# CH32X315MCU-R0.net
KiCad netlist of a schematic drawn in Altium Designer
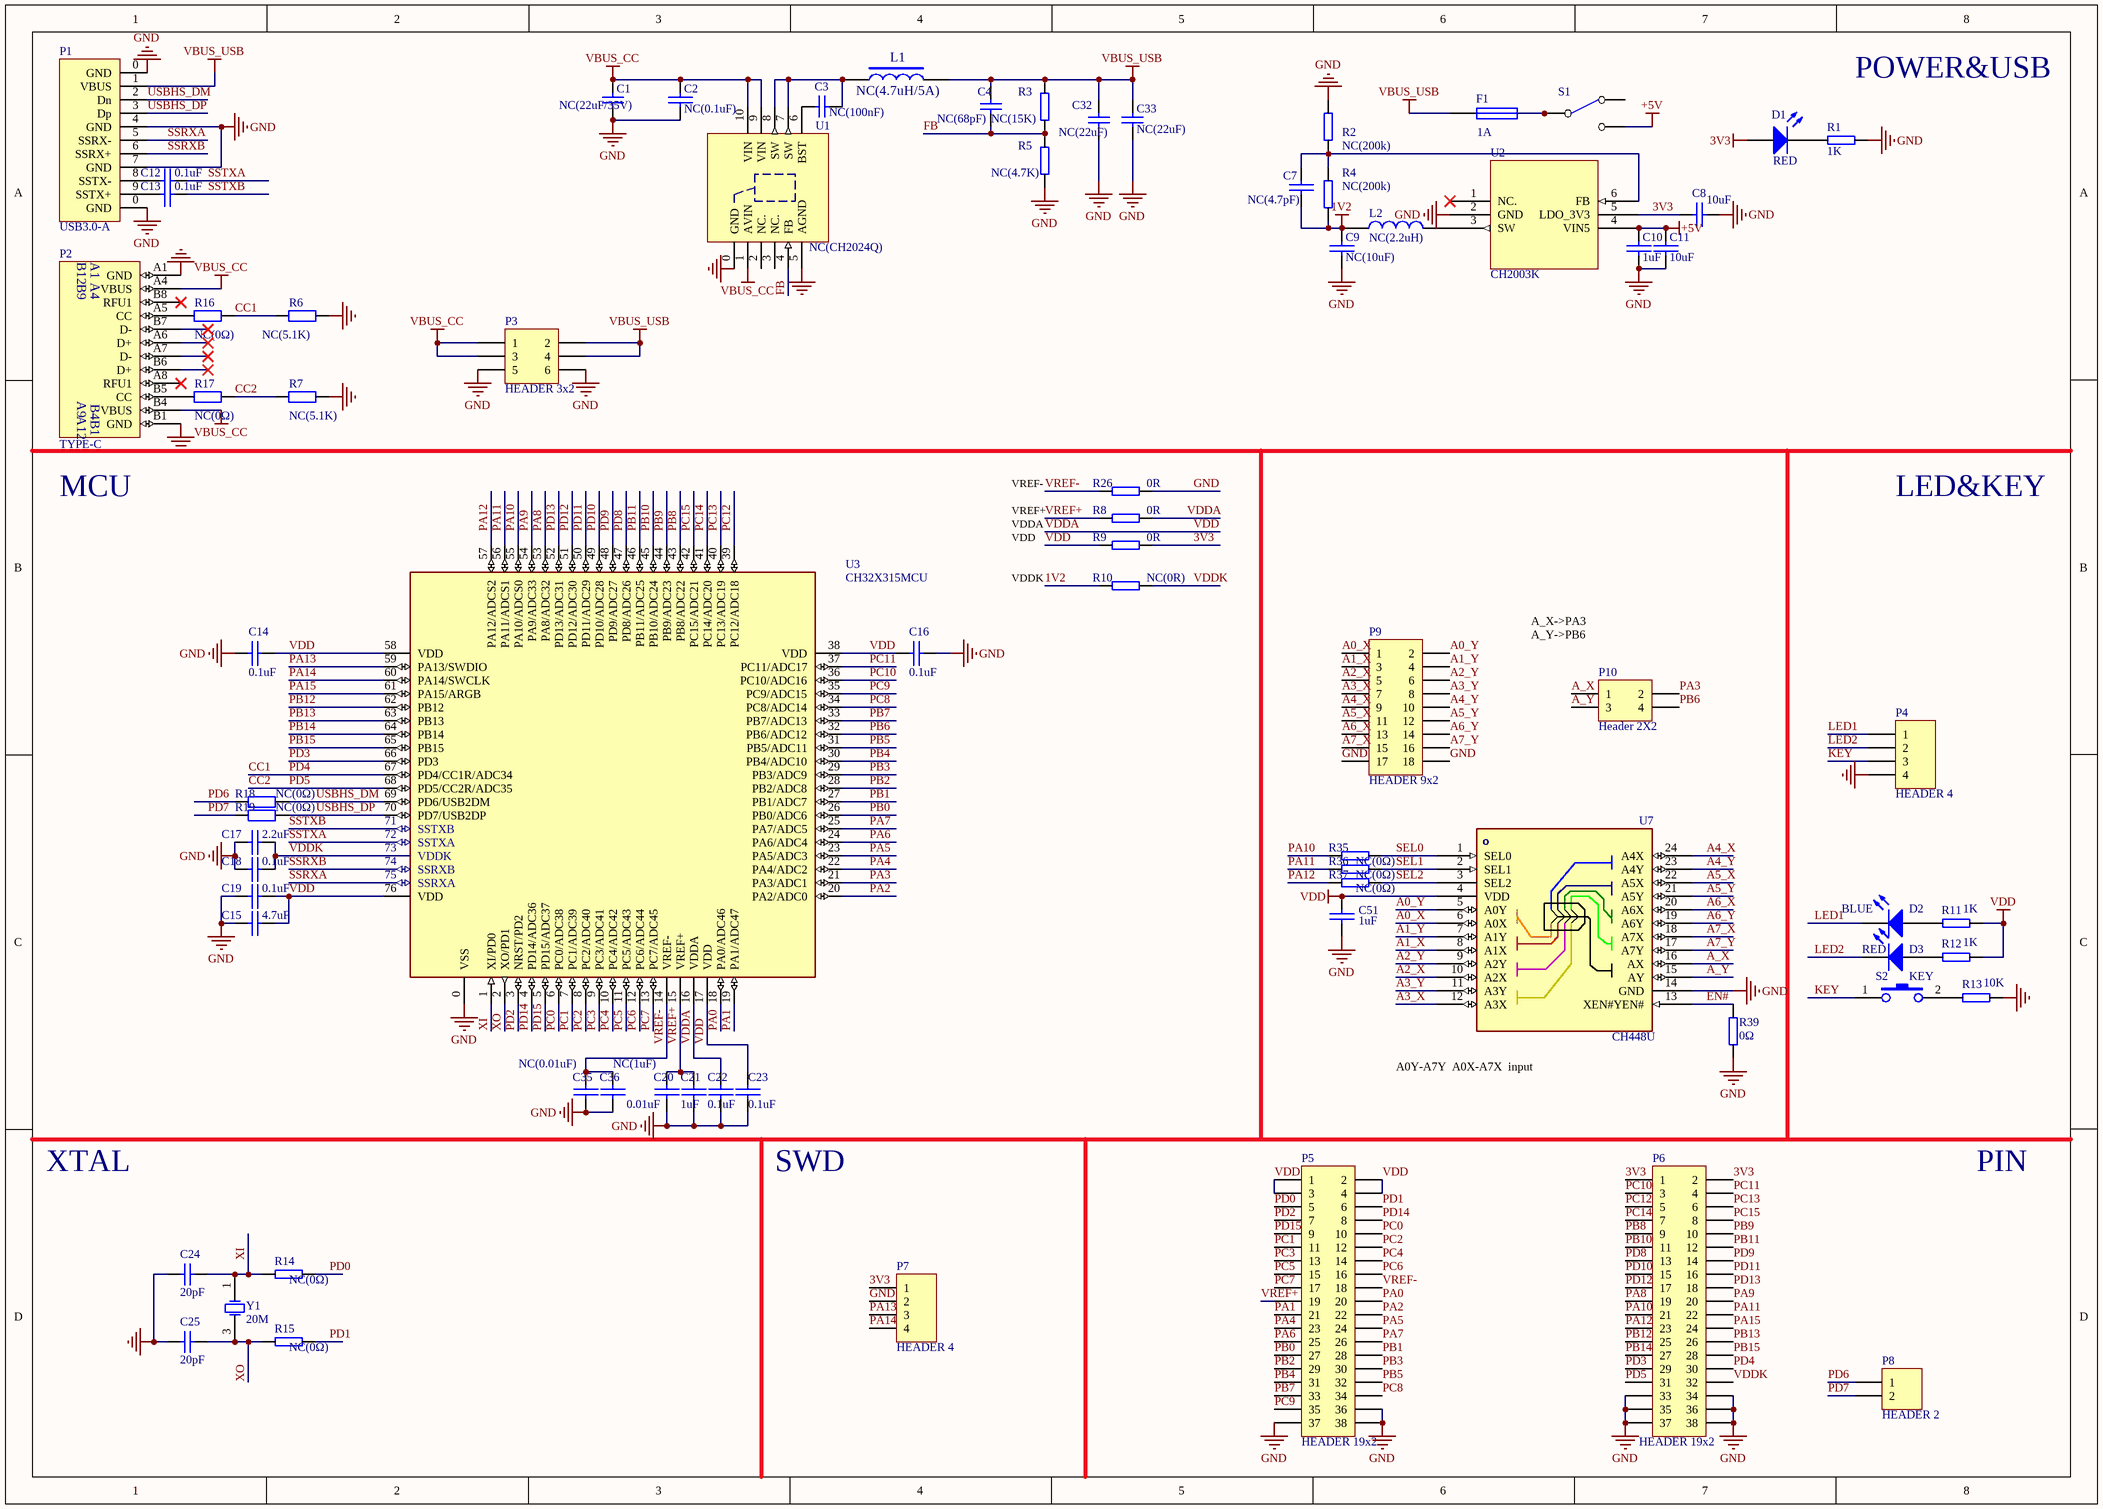
[diagram p0: CH32X315MCU-R0.SchDoc]

(export (version "E")
  (design (tool "Eeschema 10.0.6"))
  (components
    (comp (ref "C1")
      (value "NC(22uF/35V)")
      (footprint "0805_C")
      (description "贴片电容")
      (libsource (lib "Miscellaneous Devices LC") (part "0603 100nF (104) 10% 50V"))
    )
    (comp (ref "C2")
      (value "NC(0.1uF)")
      (footprint "0402_C")
      (description "Capacitor")
      (libsource (lib "") (part "CAP_1"))
    )
    (comp (ref "C3")
      (value "NC(100nF)")
      (footprint "0402_C")
      (description "贴片电容")
      (libsource (lib "Miscellaneous Devices LC") (part "0603 1uF (105) 10% 50V"))
    )
    (comp (ref "C4")
      (value "NC(68pF)")
      (footprint "0402_C")
      (description "贴片电容")
      (libsource (lib "Miscellaneous Devices LC") (part "0603 100nF (104) 10% 50V"))
    )
    (comp (ref "C7")
      (value "NC(4.7pF)")
      (footprint "0402_C")
      (description "Capacitor")
      (libsource (lib "*") (part "CAP"))
    )
    (comp (ref "C8")
      (value "10uF")
      (footprint "0603_C")
      (description "Capacitor")
      (libsource (lib "") (part "CAP_1"))
    )
    (comp (ref "C9")
      (value "NC(10uF)")
      (footprint "0603_C")
      (description "Capacitor")
      (libsource (lib "") (part "CAP_1"))
    )
    (comp (ref "C10")
      (value "1uF")
      (footprint "0402_C")
      (description "Capacitor")
      (libsource (lib "*") (part "CAP"))
    )
    (comp (ref "C11")
      (value "10uF")
      (footprint "0603_C")
      (description "Capacitor")
      (libsource (lib "") (part "CAP_1"))
    )
    (comp (ref "C12")
      (value "0.1uF")
      (footprint "0402_C")
      (description "Capacitor")
      (libsource (lib "") (part "CAP_1"))
    )
    (comp (ref "C13")
      (value "0.1uF")
      (footprint "0402_C")
      (description "Capacitor")
      (libsource (lib "") (part "CAP_1"))
    )
    (comp (ref "C14")
      (value "0.1uF")
      (footprint "0402_C")
      (description "Capacitor")
      (libsource (lib "*") (part "CAP"))
    )
    (comp (ref "C15")
      (value "4.7uF")
      (footprint "0402_C")
      (description "Capacitor")
      (libsource (lib "*") (part "CAP"))
    )
    (comp (ref "C16")
      (value "0.1uF")
      (footprint "0402_C")
      (description "Capacitor")
      (libsource (lib "*") (part "CAP"))
    )
    (comp (ref "C17")
      (value "2.2uF")
      (footprint "0402_C")
      (description "Capacitor")
      (libsource (lib "*") (part "CAP"))
    )
    (comp (ref "C18")
      (value "0.1uF")
      (footprint "0402_C")
      (description "Capacitor")
      (libsource (lib "*") (part "CAP"))
    )
    (comp (ref "C19")
      (value "0.1uF")
      (footprint "0402_C")
      (description "Capacitor")
      (libsource (lib "*") (part "CAP"))
    )
    (comp (ref "C20")
      (value "0.01uF")
      (footprint "0402_C")
      (description "Capacitor")
      (libsource (lib "*") (part "CAP"))
    )
    (comp (ref "C21")
      (value "1uF")
      (footprint "0402_C")
      (description "Capacitor")
      (libsource (lib "*") (part "CAP"))
    )
    (comp (ref "C22")
      (value "0.1uF")
      (footprint "0402_C")
      (description "Capacitor")
      (libsource (lib "*") (part "CAP"))
    )
    (comp (ref "C23")
      (value "0.1uF")
      (footprint "0402_C")
      (description "Capacitor")
      (libsource (lib "*") (part "CAP"))
    )
    (comp (ref "C24")
      (value "20pF")
      (footprint "0402_C")
      (description "Capacitor")
      (libsource (lib "Miscellaneous Devices") (part "Cap"))
    )
    (comp (ref "C25")
      (value "20pF")
      (footprint "0402_C")
      (description "Capacitor")
      (libsource (lib "Miscellaneous Devices") (part "Cap"))
    )
    (comp (ref "C32")
      (value "NC(22uF)")
      (footprint "0805_C")
      (description "贴片电容")
      (libsource (lib "Miscellaneous Devices LC") (part "0603 100nF (104) 10% 50V"))
    )
    (comp (ref "C33")
      (value "NC(22uF)")
      (footprint "0805_C")
      (description "贴片电容")
      (libsource (lib "Miscellaneous Devices LC") (part "0603 100nF (104) 10% 50V"))
    )
    (comp (ref "C35")
      (value "NC(0.01uF)")
      (footprint "0402_C")
      (description "Capacitor")
      (libsource (lib "*") (part "CAP"))
    )
    (comp (ref "C36")
      (value "NC(1uF)")
      (footprint "0402_C")
      (description "Capacitor")
      (libsource (lib "*") (part "CAP"))
    )
    (comp (ref "C51")
      (value "1uF")
      (footprint "0402_C")
      (description "Capacitor")
      (libsource (lib "wch_sch_others") (part "CAP"))
    )
    (comp (ref "D1")
      (value "RED")
      (footprint "0603+")
      (description "Typical INFRARED GaAs LED")
      (fields (field (name "PUBLISHER") "Altium Limited"))
      (libsource (lib "*") (part "LED0"))
    )
    (comp (ref "D2")
      (value "BLUE")
      (footprint "0603+")
      (description "Typical INFRARED GaAs LED")
      (fields (field (name "PUBLISHER") "Altium Limited"))
      (libsource (lib "*") (part "LED0"))
    )
    (comp (ref "D3")
      (value "RED")
      (footprint "0603+")
      (description "Typical INFRARED GaAs LED")
      (fields (field (name "PUBLISHER") "Altium Limited"))
      (libsource (lib "*") (part "LED0"))
    )
    (comp (ref "F1")
      (value "1A")
      (footprint "0603")
      (description "Fuse")
      (libsource (lib "wch_sch_others") (part "FUSE1"))
    )
    (comp (ref "L1")
      (value "NC(4.7uH/5A)")
      (footprint "IND-SMD_L7.0-W6.6")
      (libsource (lib "wch_sch_others") (part "INDUCTOR"))
    )
    (comp (ref "L2") (value "NC(2.2uH)") (footprint "CD32") (libsource (lib "*") (part "INDUCTOR")))
    (comp (ref "P1")
      (value "USB3.0-A")
      (footprint "USB3.0-A-Receptacle")
      (libsource (lib "wch_sch_others") (part "USB3.0-A"))
    )
    (comp (ref "P2")
      (value "TYPE-C")
      (footprint "TYPE-C-Receptacle-2.0")
      (libsource (lib "*") (part "TYPE-C1"))
    )
    (comp (ref "P3")
      (value "HEADER 3x2")
      (footprint "MYPCB:IDC6-2.54mm")
      (description "Header, 3-Pin, Dual row")
      (libsource (lib "wch_sch_others") (part "HEADER 3x2"))
    )
    (comp (ref "P4")
      (value "HEADER 4")
      (footprint "SIP4-2.54mm")
      (description "Header, 4-Pin")
      (libsource (lib "wch_sch_others") (part "HEADER 4"))
    )
    (comp (ref "P5")
      (value "HEADER 19x2")
      (footprint "MYPCB:IDC38-2.54MM")
      (description "Header, 19-Pin, Dual row")
      (libsource (lib "wch_sch_others") (part "HEADER 19x2"))
    )
    (comp (ref "P6")
      (value "HEADER 19x2")
      (footprint "MYPCB:IDC38-2.54MM")
      (description "Header, 19-Pin, Dual row")
      (libsource (lib "wch_sch_others") (part "HEADER 19x2"))
    )
    (comp (ref "P7")
      (value "HEADER 4")
      (footprint "SIP4-2.54mm")
      (description "Header, 4-Pin")
      (libsource (lib "wch_sch_others") (part "HEADER 4"))
    )
    (comp (ref "P8")
      (value "HEADER 2")
      (footprint "MYPCB:SIP2-2.54mm")
      (description "Header, 2-Pin")
      (libsource (lib "wch_sch_others") (part "HEADER 2"))
    )
    (comp (ref "P9")
      (value "HEADER 9x2")
      (footprint "MYPCB:IDC18-2.54MM")
      (description "Header, 9-Pin, Dual row")
      (libsource (lib "wch_sch_others") (part "HEADER 9x2"))
    )
    (comp (ref "P10")
      (value "Header 2X2")
      (footprint "IDC4-2.54mm")
      (description "Header, 2-Pin, Dual row")
      (fields (field (name "PUBLISHER") "Altium Limited"))
      (libsource (lib "Miscellaneous Connectors") (part "Header 2X2"))
    )
    (comp (ref "R1") (value "1K") (footprint "0402") (libsource (lib "") (part "RES_1")))
    (comp (ref "R2") (value "NC(200k)") (footprint "0402") (libsource (lib "wch_sch_others") (part "RES")))
    (comp (ref "R3") (value "NC(15K)") (footprint "0402") (libsource (lib "wch_sch_others(1)") (part "RES")))
    (comp (ref "R4") (value "NC(200k)") (footprint "0402") (libsource (lib "wch_sch_others") (part "RES")))
    (comp (ref "R5") (value "NC(4.7K)") (footprint "0402") (libsource (lib "wch_sch_others(1)") (part "RES")))
    (comp (ref "R6")
      (value "NC(5.1K)")
      (footprint "0402")
      (description "Resistor")
      (libsource (lib "") (part "Res2_1"))
    )
    (comp (ref "R7")
      (value "NC(5.1K)")
      (footprint "0402")
      (description "Resistor")
      (libsource (lib "") (part "Res2_1"))
    )
    (comp (ref "R8") (value "0R") (footprint "0402") (libsource (lib "*") (part "R")))
    (comp (ref "R9") (value "0R") (footprint "0402") (libsource (lib "*") (part "R")))
    (comp (ref "R10") (value "NC(0R)") (footprint "0402") (libsource (lib "*") (part "R")))
    (comp (ref "R11") (value "1K") (footprint "0402") (libsource (lib "") (part "RES_1")))
    (comp (ref "R12") (value "1K") (footprint "0402") (libsource (lib "") (part "RES_1")))
    (comp (ref "R13") (value "10K") (footprint "0402") (libsource (lib "") (part "RES_1")))
    (comp (ref "R14") (value "NC(0Ω)") (footprint "0402") (libsource (lib "wch_sch_others") (part "RES")))
    (comp (ref "R15") (value "NC(0Ω)") (footprint "0402") (libsource (lib "wch_sch_others") (part "RES")))
    (comp (ref "R16")
      (value "NC(0Ω)")
      (footprint "0402")
      (description "Resistor")
      (libsource (lib "") (part "Res2_1"))
    )
    (comp (ref "R17")
      (value "NC(0Ω)")
      (footprint "0402")
      (description "Resistor")
      (libsource (lib "") (part "Res2_1"))
    )
    (comp (ref "R18")
      (value "NC(0Ω)")
      (footprint "0402")
      (description "Resistor")
      (libsource (lib "Miscellaneous Devices") (part "Res2"))
    )
    (comp (ref "R19")
      (value "NC(0Ω)")
      (footprint "0402")
      (description "Resistor")
      (libsource (lib "Miscellaneous Devices") (part "Res2"))
    )
    (comp (ref "R26") (value "0R") (footprint "0402") (libsource (lib "*") (part "R")))
    (comp (ref "R35") (value "NC(0Ω)") (footprint "0402") (libsource (lib "wch_sch_others") (part "RES")))
    (comp (ref "R36") (value "NC(0Ω)") (footprint "0402") (libsource (lib "wch_sch_others") (part "RES")))
    (comp (ref "R37") (value "NC(0Ω)") (footprint "0402") (libsource (lib "wch_sch_others") (part "RES")))
    (comp (ref "R39") (value "0Ω") (footprint "0402") (libsource (lib "wch_sch_others") (part "RES")))
    (comp (ref "S1") (value "SW SPDT") (footprint "SW1") (libsource (lib "*") (part "SW SPDT")))
    (comp (ref "S2")
      (value "KEY")
      (footprint "SMD_6.1x3.65x2.5mm-KEY")
      (libsource (lib "wch_sch_others") (part "KEY1"))
    )
    (comp (ref "U1")
      (value "NC(CH2024Q)")
      (footprint "DFN10_3X3")
      (description "Step-Down DC-DC Converter, 28V input, FB 1.2V, 3A output")
      (libsource (lib "DHXXXSCH") (part "CH2024Q"))
    )
    (comp (ref "U2")
      (value "CH2003K")
      (footprint "SOT-23-6")
      (description "Step-Down DC-DC Converter, 5V input, FB 0.6V, 800mA output, with LDO 3.3V * 200mA")
      (libsource (lib "DHXXXSCH") (part "CH2003K"))
    )
    (comp (ref "U3")
      (value "CH32X315MCU")
      (footprint "QFN76_9X9")
      (description "RISC-V FPU MCU, 480MHz, USB3.0_5Gbps, PD, HSADC")
      (libsource (lib "DHXXXSCH") (part "CH32X315MCU"))
    )
    (comp (ref "U7")
      (value "CH448U")
      (footprint "QSOP24")
      (description "USB2.0 mux 8:1 / 16:1 Differential Switch, DPOT with dual enable")
      (libsource (lib "CH448U") (part "CH448U"))
    )
    (comp (ref "Y1")
      (value "20M")
      (footprint "XT3225")
      (description "Crystal Oscillator")
      (fields (field (name "PUBLISHER") "Altium Limited"))
      (libsource (lib "Miscellaneous Devices") (part "XTAL"))
    )
  )
  (nets
    (net (code "1") (name "+5V") (class "Default")
      (node (ref "C10") (pin "2") (pinfunction "2_2") (pintype "passive"))
      (node (ref "C11") (pin "2") (pinfunction "2_2") (pintype "passive"))
      (node (ref "S1") (pin "2") (pinfunction "NC_2") (pintype "passive"))
      (node (ref "U2") (pin "4") (pinfunction "VIN5_4") (pintype "power_in"))
    )
    (net (code "3") (name "/A0_X") (class "Default")
      (node (ref "P9") (pin "1") (pinfunction "1_1") (pintype "passive"))
      (node (ref "U7") (pin "6") (pinfunction "A0X_6") (pintype "bidirectional"))
    )
    (net (code "4") (name "/A0_Y") (class "Default")
      (node (ref "P9") (pin "2") (pinfunction "2_2") (pintype "passive"))
      (node (ref "U7") (pin "5") (pinfunction "A0Y_5") (pintype "bidirectional"))
    )
    (net (code "5") (name "/A1_X") (class "Default")
      (node (ref "P9") (pin "3") (pinfunction "3_3") (pintype "passive"))
      (node (ref "U7") (pin "8") (pinfunction "A1X_8") (pintype "bidirectional"))
    )
    (net (code "6") (name "/A1_Y") (class "Default")
      (node (ref "P9") (pin "4") (pinfunction "4_4") (pintype "passive"))
      (node (ref "U7") (pin "7") (pinfunction "A1Y_7") (pintype "bidirectional"))
    )
    (net (code "7") (name "/A2_X") (class "Default")
      (node (ref "P9") (pin "5") (pinfunction "5_5") (pintype "passive"))
      (node (ref "U7") (pin "10") (pinfunction "A2X_10") (pintype "bidirectional"))
    )
    (net (code "8") (name "/A2_Y") (class "Default")
      (node (ref "P9") (pin "6") (pinfunction "6_6") (pintype "passive"))
      (node (ref "U7") (pin "9") (pinfunction "A2Y_9") (pintype "bidirectional"))
    )
    (net (code "9") (name "/A3_X") (class "Default")
      (node (ref "P9") (pin "7") (pinfunction "7_7") (pintype "passive"))
      (node (ref "U7") (pin "12") (pinfunction "A3X_12") (pintype "bidirectional"))
    )
    (net (code "10") (name "/A3_Y") (class "Default")
      (node (ref "P9") (pin "8") (pinfunction "8_8") (pintype "passive"))
      (node (ref "U7") (pin "11") (pinfunction "A3Y_11") (pintype "bidirectional"))
    )
    (net (code "11") (name "/A4_X") (class "Default")
      (node (ref "P9") (pin "9") (pinfunction "9_9") (pintype "passive"))
      (node (ref "U7") (pin "24") (pinfunction "A4X_24") (pintype "bidirectional"))
    )
    (net (code "12") (name "/A4_Y") (class "Default")
      (node (ref "P9") (pin "10") (pinfunction "10_10") (pintype "passive"))
      (node (ref "U7") (pin "23") (pinfunction "A4Y_23") (pintype "bidirectional"))
    )
    (net (code "13") (name "/A5_X") (class "Default")
      (node (ref "P9") (pin "11") (pinfunction "11_11") (pintype "passive"))
      (node (ref "U7") (pin "22") (pinfunction "A5X_22") (pintype "bidirectional"))
    )
    (net (code "14") (name "/A5_Y") (class "Default")
      (node (ref "P9") (pin "12") (pinfunction "12_12") (pintype "passive"))
      (node (ref "U7") (pin "21") (pinfunction "A5Y_21") (pintype "bidirectional"))
    )
    (net (code "15") (name "/A6_X") (class "Default")
      (node (ref "P9") (pin "13") (pinfunction "13_13") (pintype "passive"))
      (node (ref "U7") (pin "20") (pinfunction "A6X_20") (pintype "bidirectional"))
    )
    (net (code "16") (name "/A6_Y") (class "Default")
      (node (ref "P9") (pin "14") (pinfunction "14_14") (pintype "passive"))
      (node (ref "U7") (pin "19") (pinfunction "A6Y_19") (pintype "bidirectional"))
    )
    (net (code "17") (name "/A7_X") (class "Default")
      (node (ref "P9") (pin "15") (pinfunction "15_15") (pintype "passive"))
      (node (ref "U7") (pin "18") (pinfunction "A7X_18") (pintype "bidirectional"))
    )
    (net (code "18") (name "/A7_Y") (class "Default")
      (node (ref "P9") (pin "16") (pinfunction "16_16") (pintype "passive"))
      (node (ref "U7") (pin "17") (pinfunction "A7Y_17") (pintype "bidirectional"))
    )
    (net (code "19") (name "/A_X") (class "Default")
      (node (ref "P10") (pin "1") (pinfunction "1_1") (pintype "passive"))
      (node (ref "U7") (pin "16") (pinfunction "AX_16") (pintype "bidirectional"))
    )
    (net (code "20") (name "/A_Y") (class "Default")
      (node (ref "P10") (pin "3") (pinfunction "3_3") (pintype "passive"))
      (node (ref "U7") (pin "15") (pinfunction "AY_15") (pintype "bidirectional"))
    )
    (net (code "21") (name "/CC1") (class "Default")
      (node (ref "P6") (pin "30") (pinfunction "30_30") (pintype "passive"))
      (node (ref "R16") (pin "2") (pinfunction "2_2") (pintype "passive"))
      (node (ref "R6") (pin "1") (pinfunction "1_1") (pintype "passive"))
      (node (ref "U3") (pin "67") (pinfunction "PD4/CC1R/ADC34_67") (pintype "bidirectional"))
    )
    (net (code "22") (name "/CC2") (class "Default")
      (node (ref "P6") (pin "31") (pinfunction "31_31") (pintype "passive"))
      (node (ref "R17") (pin "2") (pinfunction "2_2") (pintype "passive"))
      (node (ref "R7") (pin "1") (pinfunction "1_1") (pintype "passive"))
      (node (ref "U3") (pin "68") (pinfunction "PD5/CC2R/ADC35_68") (pintype "bidirectional"))
    )
    (net (code "23") (name "/EN#") (class "Default")
      (node (ref "R39") (pin "2") (pintype "passive"))
      (node (ref "U7") (pin "13") (pinfunction "XEN#YEN#_13") (pintype "input"))
    )
    (net (code "24") (name "/FB") (class "Default")
      (node (ref "C4") (pin "2") (pinfunction "2_2") (pintype "passive"))
      (node (ref "R3") (pin "1") (pintype "passive"))
      (node (ref "R5") (pin "2") (pintype "passive"))
      (node (ref "U1") (pin "4") (pinfunction "FB_4") (pintype "input"))
    )
    (net (code "25") (name "/KEY") (class "Default")
      (node (ref "P4") (pin "3") (pinfunction "3_3") (pintype "passive"))
      (node (ref "S2") (pin "1") (pinfunction "1_1") (pintype "passive"))
    )
    (net (code "26") (name "/LED1") (class "Default")
      (node (ref "D2") (pin "2") (pinfunction "K_2") (pintype "passive"))
      (node (ref "P4") (pin "1") (pinfunction "1_1") (pintype "passive"))
    )
    (net (code "27") (name "/LED2") (class "Default")
      (node (ref "D3") (pin "2") (pinfunction "K_2") (pintype "passive"))
      (node (ref "P4") (pin "2") (pinfunction "2_2") (pintype "passive"))
    )
    (net (code "28") (name "/PA0") (class "Default")
      (node (ref "P5") (pin "20") (pinfunction "20_20") (pintype "passive"))
      (node (ref "U3") (pin "18") (pinfunction "PA0/ADC46_18") (pintype "bidirectional"))
    )
    (net (code "29") (name "/PA1") (class "Default")
      (node (ref "P5") (pin "21") (pinfunction "21_21") (pintype "passive"))
      (node (ref "U3") (pin "19") (pinfunction "PA1/ADC47_19") (pintype "bidirectional"))
    )
    (net (code "30") (name "/PA2") (class "Default")
      (node (ref "P5") (pin "22") (pinfunction "22_22") (pintype "passive"))
      (node (ref "U3") (pin "20") (pinfunction "PA2/ADC0_20") (pintype "bidirectional"))
    )
    (net (code "31") (name "/PA3") (class "Default")
      (node (ref "P10") (pin "2") (pinfunction "2_2") (pintype "passive"))
      (node (ref "U3") (pin "21") (pinfunction "PA3/ADC1_21") (pintype "bidirectional"))
    )
    (net (code "32") (name "/PA4") (class "Default")
      (node (ref "P5") (pin "23") (pinfunction "23_23") (pintype "passive"))
      (node (ref "U3") (pin "22") (pinfunction "PA4/ADC2_22") (pintype "bidirectional"))
    )
    (net (code "33") (name "/PA5") (class "Default")
      (node (ref "P5") (pin "24") (pinfunction "24_24") (pintype "passive"))
      (node (ref "U3") (pin "23") (pinfunction "PA5/ADC3_23") (pintype "bidirectional"))
    )
    (net (code "34") (name "/PA6") (class "Default")
      (node (ref "P5") (pin "25") (pinfunction "25_25") (pintype "passive"))
      (node (ref "U3") (pin "24") (pinfunction "PA6/ADC4_24") (pintype "bidirectional"))
    )
    (net (code "35") (name "/PA7") (class "Default")
      (node (ref "P5") (pin "26") (pinfunction "26_26") (pintype "passive"))
      (node (ref "U3") (pin "25") (pinfunction "PA7/ADC5_25") (pintype "bidirectional"))
    )
    (net (code "36") (name "/PA8") (class "Default")
      (node (ref "P6") (pin "19") (pinfunction "19_19") (pintype "passive"))
      (node (ref "U3") (pin "53") (pinfunction "PA8/ADC32_53") (pintype "bidirectional"))
    )
    (net (code "37") (name "/PA9") (class "Default")
      (node (ref "P6") (pin "20") (pinfunction "20_20") (pintype "passive"))
      (node (ref "U3") (pin "54") (pinfunction "PA9/ADC33_54") (pintype "bidirectional"))
    )
    (net (code "38") (name "/PA10") (class "Default")
      (node (ref "P6") (pin "21") (pinfunction "21_21") (pintype "passive"))
      (node (ref "R35") (pin "2") (pintype "passive"))
      (node (ref "U3") (pin "55") (pinfunction "PA10/ADCS0_55") (pintype "bidirectional"))
    )
    (net (code "39") (name "/PA11") (class "Default")
      (node (ref "P6") (pin "22") (pinfunction "22_22") (pintype "passive"))
      (node (ref "R36") (pin "2") (pintype "passive"))
      (node (ref "U3") (pin "56") (pinfunction "PA11/ADCS1_56") (pintype "bidirectional"))
    )
    (net (code "40") (name "/PA12") (class "Default")
      (node (ref "P6") (pin "23") (pinfunction "23_23") (pintype "passive"))
      (node (ref "R37") (pin "2") (pintype "passive"))
      (node (ref "U3") (pin "57") (pinfunction "PA12/ADCS2_57") (pintype "bidirectional"))
    )
    (net (code "41") (name "/PA13") (class "Default")
      (node (ref "P7") (pin "3") (pinfunction "3_3") (pintype "passive"))
      (node (ref "U3") (pin "59") (pinfunction "PA13/SWDIO_59") (pintype "bidirectional"))
    )
    (net (code "42") (name "/PA14") (class "Default")
      (node (ref "P7") (pin "4") (pinfunction "4_4") (pintype "passive"))
      (node (ref "U3") (pin "60") (pinfunction "PA14/SWCLK_60") (pintype "bidirectional"))
    )
    (net (code "43") (name "/PA15") (class "Default")
      (node (ref "P6") (pin "24") (pinfunction "24_24") (pintype "passive"))
      (node (ref "U3") (pin "61") (pinfunction "PA15/ARGB_61") (pintype "bidirectional"))
    )
    (net (code "44") (name "/PB0") (class "Default")
      (node (ref "P5") (pin "27") (pinfunction "27_27") (pintype "passive"))
      (node (ref "U3") (pin "26") (pinfunction "PB0/ADC6_26") (pintype "bidirectional"))
    )
    (net (code "45") (name "/PB1") (class "Default")
      (node (ref "P5") (pin "28") (pinfunction "28_28") (pintype "passive"))
      (node (ref "U3") (pin "27") (pinfunction "PB1/ADC7_27") (pintype "bidirectional"))
    )
    (net (code "46") (name "/PB2") (class "Default")
      (node (ref "P5") (pin "29") (pinfunction "29_29") (pintype "passive"))
      (node (ref "U3") (pin "28") (pinfunction "PB2/ADC8_28") (pintype "bidirectional"))
    )
    (net (code "47") (name "/PB3") (class "Default")
      (node (ref "P5") (pin "30") (pinfunction "30_30") (pintype "passive"))
      (node (ref "U3") (pin "29") (pinfunction "PB3/ADC9_29") (pintype "bidirectional"))
    )
    (net (code "48") (name "/PB4") (class "Default")
      (node (ref "P5") (pin "31") (pinfunction "31_31") (pintype "passive"))
      (node (ref "U3") (pin "30") (pinfunction "PB4/ADC10_30") (pintype "bidirectional"))
    )
    (net (code "49") (name "/PB5") (class "Default")
      (node (ref "P5") (pin "32") (pinfunction "32_32") (pintype "passive"))
      (node (ref "U3") (pin "31") (pinfunction "PB5/ADC11_31") (pintype "bidirectional"))
    )
    (net (code "50") (name "/PB6") (class "Default")
      (node (ref "P10") (pin "4") (pinfunction "4_4") (pintype "passive"))
      (node (ref "U3") (pin "32") (pinfunction "PB6/ADC12_32") (pintype "bidirectional"))
    )
    (net (code "51") (name "/PB7") (class "Default")
      (node (ref "P5") (pin "33") (pinfunction "33_33") (pintype "passive"))
      (node (ref "U3") (pin "33") (pinfunction "PB7/ADC13_33") (pintype "bidirectional"))
    )
    (net (code "52") (name "/PB8") (class "Default")
      (node (ref "P6") (pin "9") (pinfunction "9_9") (pintype "passive"))
      (node (ref "U3") (pin "43") (pinfunction "PB8/ADC22_43") (pintype "bidirectional"))
    )
    (net (code "53") (name "/PB9") (class "Default")
      (node (ref "P6") (pin "10") (pinfunction "10_10") (pintype "passive"))
      (node (ref "U3") (pin "44") (pinfunction "PB9/ADC23_44") (pintype "bidirectional"))
    )
    (net (code "54") (name "/PB10") (class "Default")
      (node (ref "P6") (pin "11") (pinfunction "11_11") (pintype "passive"))
      (node (ref "U3") (pin "45") (pinfunction "PB10/ADC24_45") (pintype "bidirectional"))
    )
    (net (code "55") (name "/PB11") (class "Default")
      (node (ref "P6") (pin "12") (pinfunction "12_12") (pintype "passive"))
      (node (ref "U3") (pin "46") (pinfunction "PB11/ADC25_46") (pintype "bidirectional"))
    )
    (net (code "56") (name "/PB12") (class "Default")
      (node (ref "P6") (pin "25") (pinfunction "25_25") (pintype "passive"))
      (node (ref "U3") (pin "62") (pinfunction "PB12_62") (pintype "bidirectional"))
    )
    (net (code "57") (name "/PB13") (class "Default")
      (node (ref "P6") (pin "26") (pinfunction "26_26") (pintype "passive"))
      (node (ref "U3") (pin "63") (pinfunction "PB13_63") (pintype "bidirectional"))
    )
    (net (code "58") (name "/PB14") (class "Default")
      (node (ref "P6") (pin "27") (pinfunction "27_27") (pintype "passive"))
      (node (ref "U3") (pin "64") (pinfunction "PB14_64") (pintype "bidirectional"))
    )
    (net (code "59") (name "/PB15") (class "Default")
      (node (ref "P6") (pin "28") (pinfunction "28_28") (pintype "passive"))
      (node (ref "U3") (pin "65") (pinfunction "PB15_65") (pintype "bidirectional"))
    )
    (net (code "60") (name "/PC0") (class "Default")
      (node (ref "P5") (pin "10") (pinfunction "10_10") (pintype "passive"))
      (node (ref "U3") (pin "6") (pinfunction "PC0/ADC38_6") (pintype "bidirectional"))
    )
    (net (code "61") (name "/PC1") (class "Default")
      (node (ref "P5") (pin "11") (pinfunction "11_11") (pintype "passive"))
      (node (ref "U3") (pin "7") (pinfunction "PC1/ADC39_7") (pintype "bidirectional"))
    )
    (net (code "62") (name "/PC2") (class "Default")
      (node (ref "P5") (pin "12") (pinfunction "12_12") (pintype "passive"))
      (node (ref "U3") (pin "8") (pinfunction "PC2/ADC40_8") (pintype "bidirectional"))
    )
    (net (code "63") (name "/PC3") (class "Default")
      (node (ref "P5") (pin "13") (pinfunction "13_13") (pintype "passive"))
      (node (ref "U3") (pin "9") (pinfunction "PC3/ADC41_9") (pintype "bidirectional"))
    )
    (net (code "64") (name "/PC4") (class "Default")
      (node (ref "P5") (pin "14") (pinfunction "14_14") (pintype "passive"))
      (node (ref "U3") (pin "10") (pinfunction "PC4/ADC42_10") (pintype "bidirectional"))
    )
    (net (code "65") (name "/PC5") (class "Default")
      (node (ref "P5") (pin "15") (pinfunction "15_15") (pintype "passive"))
      (node (ref "U3") (pin "11") (pinfunction "PC5/ADC43_11") (pintype "bidirectional"))
    )
    (net (code "66") (name "/PC6") (class "Default")
      (node (ref "P5") (pin "16") (pinfunction "16_16") (pintype "passive"))
      (node (ref "U3") (pin "12") (pinfunction "PC6/ADC44_12") (pintype "bidirectional"))
    )
    (net (code "67") (name "/PC7") (class "Default")
      (node (ref "P5") (pin "17") (pinfunction "17_17") (pintype "passive"))
      (node (ref "U3") (pin "13") (pinfunction "PC7/ADC45_13") (pintype "bidirectional"))
    )
    (net (code "68") (name "/PC8") (class "Default")
      (node (ref "P5") (pin "34") (pinfunction "34_34") (pintype "passive"))
      (node (ref "U3") (pin "34") (pinfunction "PC8/ADC14_34") (pintype "bidirectional"))
    )
    (net (code "69") (name "/PC9") (class "Default")
      (node (ref "P5") (pin "35") (pinfunction "35_35") (pintype "passive"))
      (node (ref "U3") (pin "35") (pinfunction "PC9/ADC15_35") (pintype "bidirectional"))
    )
    (net (code "70") (name "/PC10") (class "Default")
      (node (ref "P6") (pin "3") (pinfunction "3_3") (pintype "passive"))
      (node (ref "U3") (pin "36") (pinfunction "PC10/ADC16_36") (pintype "bidirectional"))
    )
    (net (code "71") (name "/PC11") (class "Default")
      (node (ref "P6") (pin "4") (pinfunction "4_4") (pintype "passive"))
      (node (ref "U3") (pin "37") (pinfunction "PC11/ADC17_37") (pintype "bidirectional"))
    )
    (net (code "72") (name "/PC12") (class "Default")
      (node (ref "P6") (pin "5") (pinfunction "5_5") (pintype "passive"))
      (node (ref "U3") (pin "39") (pinfunction "PC12/ADC18_39") (pintype "bidirectional"))
    )
    (net (code "73") (name "/PC13") (class "Default")
      (node (ref "P6") (pin "6") (pinfunction "6_6") (pintype "passive"))
      (node (ref "U3") (pin "40") (pinfunction "PC13/ADC19_40") (pintype "bidirectional"))
    )
    (net (code "74") (name "/PC14") (class "Default")
      (node (ref "P6") (pin "7") (pinfunction "7_7") (pintype "passive"))
      (node (ref "U3") (pin "41") (pinfunction "PC14/ADC20_41") (pintype "bidirectional"))
    )
    (net (code "75") (name "/PC15") (class "Default")
      (node (ref "P6") (pin "8") (pinfunction "8_8") (pintype "passive"))
      (node (ref "U3") (pin "42") (pinfunction "PC15/ADC21_42") (pintype "bidirectional"))
    )
    (net (code "76") (name "/PD0") (class "Default")
      (node (ref "P5") (pin "5") (pinfunction "5_5") (pintype "passive"))
      (node (ref "R14") (pin "1") (pintype "passive"))
    )
    (net (code "77") (name "/PD1") (class "Default")
      (node (ref "P5") (pin "6") (pinfunction "6_6") (pintype "passive"))
      (node (ref "R15") (pin "1") (pintype "passive"))
    )
    (net (code "78") (name "/PD2") (class "Default")
      (node (ref "P5") (pin "7") (pinfunction "7_7") (pintype "passive"))
      (node (ref "U3") (pin "3") (pinfunction "NRST/PD2_3") (pintype "bidirectional"))
    )
    (net (code "79") (name "/PD3") (class "Default")
      (node (ref "P6") (pin "29") (pinfunction "29_29") (pintype "passive"))
      (node (ref "U3") (pin "66") (pinfunction "PD3_66") (pintype "bidirectional"))
    )
    (net (code "80") (name "/PD6") (class "Default")
      (node (ref "P8") (pin "1") (pinfunction "1_1") (pintype "passive"))
      (node (ref "R18") (pin "2") (pinfunction "2_2") (pintype "passive"))
    )
    (net (code "81") (name "/PD7") (class "Default")
      (node (ref "P8") (pin "2") (pinfunction "2_2") (pintype "passive"))
      (node (ref "R19") (pin "2") (pinfunction "2_2") (pintype "passive"))
    )
    (net (code "82") (name "/PD8") (class "Default")
      (node (ref "P6") (pin "13") (pinfunction "13_13") (pintype "passive"))
      (node (ref "U3") (pin "47") (pinfunction "PD8/ADC26_47") (pintype "bidirectional"))
    )
    (net (code "83") (name "/PD9") (class "Default")
      (node (ref "P6") (pin "14") (pinfunction "14_14") (pintype "passive"))
      (node (ref "U3") (pin "48") (pinfunction "PD9/ADC27_48") (pintype "bidirectional"))
    )
    (net (code "84") (name "/PD10") (class "Default")
      (node (ref "P6") (pin "15") (pinfunction "15_15") (pintype "passive"))
      (node (ref "U3") (pin "49") (pinfunction "PD10/ADC28_49") (pintype "bidirectional"))
    )
    (net (code "85") (name "/PD11") (class "Default")
      (node (ref "P6") (pin "16") (pinfunction "16_16") (pintype "passive"))
      (node (ref "U3") (pin "50") (pinfunction "PD11/ADC29_50") (pintype "bidirectional"))
    )
    (net (code "86") (name "/PD12") (class "Default")
      (node (ref "P6") (pin "17") (pinfunction "17_17") (pintype "passive"))
      (node (ref "U3") (pin "51") (pinfunction "PD12/ADC30_51") (pintype "bidirectional"))
    )
    (net (code "87") (name "/PD13") (class "Default")
      (node (ref "P6") (pin "18") (pinfunction "18_18") (pintype "passive"))
      (node (ref "U3") (pin "52") (pinfunction "PD13/ADC31_52") (pintype "bidirectional"))
    )
    (net (code "88") (name "/PD14") (class "Default")
      (node (ref "P5") (pin "8") (pinfunction "8_8") (pintype "passive"))
      (node (ref "U3") (pin "4") (pinfunction "PD14/ADC36_4") (pintype "bidirectional"))
    )
    (net (code "89") (name "/PD15") (class "Default")
      (node (ref "P5") (pin "9") (pinfunction "9_9") (pintype "passive"))
      (node (ref "U3") (pin "5") (pinfunction "PD15/ADC37_5") (pintype "bidirectional"))
    )
    (net (code "90") (name "/SEL0") (class "Default")
      (node (ref "R35") (pin "1") (pintype "passive"))
      (node (ref "U7") (pin "1") (pinfunction "SEL0_1") (pintype "input"))
    )
    (net (code "91") (name "/SEL1") (class "Default")
      (node (ref "R36") (pin "1") (pintype "passive"))
      (node (ref "U7") (pin "2") (pinfunction "SEL1_2") (pintype "input"))
    )
    (net (code "92") (name "/SEL2") (class "Default")
      (node (ref "R37") (pin "1") (pintype "passive"))
      (node (ref "U7") (pin "3") (pinfunction "SEL2_3") (pintype "power_in"))
    )
    (net (code "93") (name "/SSRXA") (class "Default")
      (node (ref "P1") (pin "5") (pinfunction "SSRX-_5") (pintype "passive"))
      (node (ref "U3") (pin "75") (pinfunction "SSRXA_75") (pintype "bidirectional"))
    )
    (net (code "94") (name "/SSRXB") (class "Default")
      (node (ref "P1") (pin "6") (pinfunction "SSRX+_6") (pintype "passive"))
      (node (ref "U3") (pin "74") (pinfunction "SSRXB_74") (pintype "bidirectional"))
    )
    (net (code "95") (name "/SSTXA") (class "Default")
      (node (ref "C12") (pin "2") (pinfunction "2_2") (pintype "passive"))
      (node (ref "U3") (pin "72") (pinfunction "SSTXA_72") (pintype "bidirectional"))
    )
    (net (code "96") (name "/SSTXB") (class "Default")
      (node (ref "C13") (pin "2") (pinfunction "2_2") (pintype "passive"))
      (node (ref "U3") (pin "71") (pinfunction "SSTXB_71") (pintype "bidirectional"))
    )
    (net (code "97") (name "/USBHS_DM") (class "Default")
      (node (ref "P1") (pin "2") (pinfunction "Dn_2") (pintype "passive"))
      (node (ref "R18") (pin "1") (pinfunction "1_1") (pintype "passive"))
      (node (ref "U3") (pin "69") (pinfunction "PD6/USB2DM_69") (pintype "bidirectional"))
    )
    (net (code "98") (name "/USBHS_DP") (class "Default")
      (node (ref "P1") (pin "3") (pinfunction "Dp_3") (pintype "passive"))
      (node (ref "R19") (pin "1") (pinfunction "1_1") (pintype "passive"))
      (node (ref "U3") (pin "70") (pinfunction "PD7/USB2DP_70") (pintype "bidirectional"))
    )
    (net (code "99") (name "/VDDK") (class "Default")
      (node (ref "C17") (pin "1") (pinfunction "1_1") (pintype "passive"))
      (node (ref "C18") (pin "1") (pinfunction "1_1") (pintype "passive"))
      (node (ref "P6") (pin "32") (pinfunction "32_32") (pintype "passive"))
      (node (ref "R10") (pin "1") (pinfunction "1_1") (pintype "passive"))
      (node (ref "U3") (pin "73") (pinfunction "VDDK_73") (pintype "power_in"))
    )
    (net (code "100") (name "/VREF+") (class "Default")
      (node (ref "C20") (pin "1") (pinfunction "1_1") (pintype "passive"))
      (node (ref "C21") (pin "1") (pinfunction "1_1") (pintype "passive"))
      (node (ref "P5") (pin "19") (pinfunction "19_19") (pintype "passive"))
      (node (ref "R8") (pin "2") (pinfunction "2_2") (pintype "passive"))
      (node (ref "U3") (pin "15") (pinfunction "VREF+_15") (pintype "power_in"))
    )
    (net (code "101") (name "/VREF-") (class "Default")
      (node (ref "C35") (pin "1") (pinfunction "1_1") (pintype "passive"))
      (node (ref "C36") (pin "1") (pinfunction "1_1") (pintype "passive"))
      (node (ref "P5") (pin "18") (pinfunction "18_18") (pintype "passive"))
      (node (ref "R26") (pin "2") (pinfunction "2_2") (pintype "passive"))
      (node (ref "U3") (pin "14") (pinfunction "VREF-_14") (pintype "power_in"))
    )
    (net (code "102") (name "/XI") (class "Default")
      (node (ref "C24") (pin "1") (pinfunction "1_1") (pintype "passive"))
      (node (ref "R14") (pin "2") (pintype "passive"))
      (node (ref "U3") (pin "1") (pinfunction "XI/PD0_1") (pintype "input"))
      (node (ref "Y1") (pin "1") (pinfunction "OSC1_1") (pintype "passive"))
    )
    (net (code "103") (name "/XO") (class "Default")
      (node (ref "C25") (pin "1") (pinfunction "1_1") (pintype "passive"))
      (node (ref "R15") (pin "2") (pintype "passive"))
      (node (ref "U3") (pin "2") (pinfunction "XO/PD1_2") (pintype "output"))
      (node (ref "Y1") (pin "3") (pinfunction "OSC2_3") (pintype "passive"))
    )
    (net (code "104") (name "1V2") (class "Default")
      (node (ref "C7") (pin "1") (pinfunction "1_1") (pintype "passive"))
      (node (ref "C9") (pin "2") (pinfunction "2_2") (pintype "passive"))
      (node (ref "L2") (pin "2") (pinfunction "2_2") (pintype "passive"))
      (node (ref "R10") (pin "2") (pinfunction "2_2") (pintype "passive"))
      (node (ref "R4") (pin "1") (pintype "passive"))
    )
    (net (code "105") (name "3V3") (class "Default")
      (node (ref "C8") (pin "2") (pinfunction "2_2") (pintype "passive"))
      (node (ref "D1") (pin "1") (pinfunction "A_1") (pintype "passive"))
      (node (ref "P6") (pin "1") (pinfunction "1_1") (pintype "passive"))
      (node (ref "P6") (pin "2") (pinfunction "2_2") (pintype "passive"))
      (node (ref "P7") (pin "1") (pinfunction "1_1") (pintype "passive"))
      (node (ref "R9") (pin "1") (pinfunction "1_1") (pintype "passive"))
      (node (ref "U2") (pin "5") (pinfunction "LDO_3V3_5") (pintype "power_in"))
    )
    (net (code "106") (name "GND") (class "Default")
      (node (ref "C1") (pin "1") (pinfunction "1_1") (pintype "passive"))
      (node (ref "C10") (pin "1") (pinfunction "1_1") (pintype "passive"))
      (node (ref "C11") (pin "1") (pinfunction "1_1") (pintype "passive"))
      (node (ref "C14") (pin "2") (pinfunction "2_2") (pintype "passive"))
      (node (ref "C15") (pin "2") (pinfunction "2_2") (pintype "passive"))
      (node (ref "C16") (pin "1") (pinfunction "1_1") (pintype "passive"))
      (node (ref "C17") (pin "2") (pinfunction "2_2") (pintype "passive"))
      (node (ref "C18") (pin "2") (pinfunction "2_2") (pintype "passive"))
      (node (ref "C19") (pin "2") (pinfunction "2_2") (pintype "passive"))
      (node (ref "C2") (pin "1") (pinfunction "1_1") (pintype "passive"))
      (node (ref "C20") (pin "2") (pinfunction "2_2") (pintype "passive"))
      (node (ref "C21") (pin "2") (pinfunction "2_2") (pintype "passive"))
      (node (ref "C22") (pin "2") (pinfunction "2_2") (pintype "passive"))
      (node (ref "C23") (pin "2") (pinfunction "2_2") (pintype "passive"))
      (node (ref "C24") (pin "2") (pinfunction "2_2") (pintype "passive"))
      (node (ref "C25") (pin "2") (pinfunction "2_2") (pintype "passive"))
      (node (ref "C32") (pin "1") (pinfunction "1_1") (pintype "passive"))
      (node (ref "C33") (pin "1") (pinfunction "1_1") (pintype "passive"))
      (node (ref "C35") (pin "2") (pinfunction "2_2") (pintype "passive"))
      (node (ref "C36") (pin "2") (pinfunction "2_2") (pintype "passive"))
      (node (ref "C51") (pin "2") (pinfunction "2_2") (pintype "passive"))
      (node (ref "C8") (pin "1") (pinfunction "1_1") (pintype "passive"))
      (node (ref "C9") (pin "1") (pinfunction "1_1") (pintype "passive"))
      (node (ref "P1") (pin "0") (pinfunction "GND_0") (pintype "passive"))
      (node (ref "P1") (pin "4") (pinfunction "GND_4") (pintype "passive"))
      (node (ref "P1") (pin "7") (pinfunction "GND_7") (pintype "passive"))
      (node (ref "P2") (pin "A1") (pinfunction "GND_A1") (pintype "bidirectional"))
      (node (ref "P2") (pin "B1") (pinfunction "GND_B1") (pintype "bidirectional"))
      (node (ref "P3") (pin "5") (pinfunction "5_5") (pintype "passive"))
      (node (ref "P3") (pin "6") (pinfunction "6_6") (pintype "passive"))
      (node (ref "P4") (pin "4") (pinfunction "4_4") (pintype "passive"))
      (node (ref "P5") (pin "36") (pinfunction "36_36") (pintype "passive"))
      (node (ref "P5") (pin "37") (pinfunction "37_37") (pintype "passive"))
      (node (ref "P5") (pin "38") (pinfunction "38_38") (pintype "passive"))
      (node (ref "P6") (pin "33") (pinfunction "33_33") (pintype "passive"))
      (node (ref "P6") (pin "34") (pinfunction "34_34") (pintype "passive"))
      (node (ref "P6") (pin "35") (pinfunction "35_35") (pintype "passive"))
      (node (ref "P6") (pin "36") (pinfunction "36_36") (pintype "passive"))
      (node (ref "P6") (pin "37") (pinfunction "37_37") (pintype "passive"))
      (node (ref "P6") (pin "38") (pinfunction "38_38") (pintype "passive"))
      (node (ref "P7") (pin "2") (pinfunction "2_2") (pintype "passive"))
      (node (ref "P9") (pin "17") (pinfunction "17_17") (pintype "passive"))
      (node (ref "P9") (pin "18") (pinfunction "18_18") (pintype "passive"))
      (node (ref "R1") (pin "2") (pintype "passive"))
      (node (ref "R13") (pin "1") (pintype "passive"))
      (node (ref "R2") (pin "2") (pintype "passive"))
      (node (ref "R26") (pin "1") (pinfunction "1_1") (pintype "passive"))
      (node (ref "R39") (pin "1") (pintype "passive"))
      (node (ref "R5") (pin "1") (pintype "passive"))
      (node (ref "R6") (pin "2") (pinfunction "2_2") (pintype "passive"))
      (node (ref "R7") (pin "2") (pinfunction "2_2") (pintype "passive"))
      (node (ref "U1") (pin "0") (pinfunction "GND_0") (pintype "power_in"))
      (node (ref "U1") (pin "5") (pinfunction "AGND_5") (pintype "power_in"))
      (node (ref "U2") (pin "2") (pinfunction "GND_2") (pintype "power_in"))
      (node (ref "U3") (pin "0") (pinfunction "VSS_0") (pintype "power_in"))
      (node (ref "U7") (pin "14") (pinfunction "GND_14") (pintype "power_in"))
    )
    (net (code "107") (name "Net-(C3-Pad2)") (class "Default")
      (node (ref "C3") (pin "2") (pinfunction "2_2") (pintype "passive"))
      (node (ref "L1") (pin "1") (pinfunction "1_1") (pintype "passive"))
      (node (ref "U1") (pin "7") (pinfunction "SW_7") (pintype "output"))
      (node (ref "U1") (pin "8") (pinfunction "SW_8") (pintype "output"))
    )
    (net (code "108") (name "Net-(D1-K)") (class "Default")
      (node (ref "D1") (pin "2") (pinfunction "K_2") (pintype "passive"))
      (node (ref "R1") (pin "1") (pintype "passive"))
    )
    (net (code "109") (name "Net-(D2-A)") (class "Default")
      (node (ref "D2") (pin "1") (pinfunction "A_1") (pintype "passive"))
      (node (ref "R11") (pin "2") (pintype "passive"))
    )
    (net (code "110") (name "Net-(D3-A)") (class "Default")
      (node (ref "D3") (pin "1") (pinfunction "A_1") (pintype "passive"))
      (node (ref "R12") (pin "2") (pintype "passive"))
    )
    (net (code "111") (name "Net-(P1-SSTX+)") (class "Default")
      (node (ref "C13") (pin "1") (pinfunction "1_1") (pintype "passive"))
      (node (ref "P1") (pin "9") (pinfunction "SSTX+_9") (pintype "passive"))
    )
    (net (code "112") (name "Net-(P1-SSTX-)") (class "Default")
      (node (ref "C12") (pin "1") (pinfunction "1_1") (pintype "passive"))
      (node (ref "P1") (pin "8") (pinfunction "SSTX-_8") (pintype "passive"))
    )
    (net (code "113") (name "Net-(P2-CC-PadA5)") (class "Default")
      (node (ref "P2") (pin "A5") (pinfunction "CC_A5") (pintype "bidirectional"))
      (node (ref "R16") (pin "1") (pinfunction "1_1") (pintype "passive"))
    )
    (net (code "114") (name "Net-(P2-CC-PadB5)") (class "Default")
      (node (ref "P2") (pin "B5") (pinfunction "CC_B5") (pintype "bidirectional"))
      (node (ref "R17") (pin "1") (pinfunction "1_1") (pintype "passive"))
    )
    (net (code "115") (name "Net-(R13-Pad2)") (class "Default")
      (node (ref "R13") (pin "2") (pintype "passive"))
      (node (ref "S2") (pin "2") (pinfunction "2_2") (pintype "passive"))
    )
    (net (code "116") (name "Net-(S1-COMMON)") (class "Default")
      (node (ref "F1") (pin "2") (pinfunction "2_2") (pintype "passive"))
      (node (ref "S1") (pin "1") (pinfunction "COMMON_1") (pintype "passive"))
    )
    (net (code "117") (name "Net-(U1-BST)") (class "Default")
      (node (ref "C3") (pin "1") (pinfunction "1_1") (pintype "passive"))
      (node (ref "U1") (pin "6") (pinfunction "BST_6") (pintype "power_in"))
    )
    (net (code "118") (name "Net-(U2-FB)") (class "Default")
      (node (ref "C7") (pin "2") (pinfunction "2_2") (pintype "passive"))
      (node (ref "R2") (pin "1") (pintype "passive"))
      (node (ref "R4") (pin "2") (pintype "passive"))
      (node (ref "U2") (pin "6") (pinfunction "FB_6") (pintype "input"))
    )
    (net (code "119") (name "Net-(U2-SW)") (class "Default")
      (node (ref "L2") (pin "1") (pinfunction "1_1") (pintype "passive"))
      (node (ref "U2") (pin "3") (pinfunction "SW_3") (pintype "output"))
    )
    (net (code "120") (name "VBUS_CC") (class "Default")
      (node (ref "C1") (pin "2") (pinfunction "2_2") (pintype "passive"))
      (node (ref "C2") (pin "2") (pinfunction "2_2") (pintype "passive"))
      (node (ref "P2") (pin "A4") (pinfunction "VBUS_A4") (pintype "bidirectional"))
      (node (ref "P2") (pin "B4") (pinfunction "VBUS_B4") (pintype "bidirectional"))
      (node (ref "P3") (pin "1") (pinfunction "1_1") (pintype "passive"))
      (node (ref "P3") (pin "3") (pinfunction "3_3") (pintype "passive"))
      (node (ref "U1") (pin "1") (pinfunction "AVIN_1") (pintype "power_in"))
      (node (ref "U1") (pin "10") (pinfunction "VIN_10") (pintype "power_in"))
      (node (ref "U1") (pin "9") (pinfunction "VIN_9") (pintype "power_in"))
    )
    (net (code "121") (name "VBUS_USB") (class "Default")
      (node (ref "C32") (pin "2") (pinfunction "2_2") (pintype "passive"))
      (node (ref "C33") (pin "2") (pinfunction "2_2") (pintype "passive"))
      (node (ref "C4") (pin "1") (pinfunction "1_1") (pintype "passive"))
      (node (ref "F1") (pin "1") (pinfunction "1_1") (pintype "passive"))
      (node (ref "L1") (pin "2") (pinfunction "2_2") (pintype "passive"))
      (node (ref "P1") (pin "1") (pinfunction "VBUS_1") (pintype "passive"))
      (node (ref "P3") (pin "2") (pinfunction "2_2") (pintype "passive"))
      (node (ref "P3") (pin "4") (pinfunction "4_4") (pintype "passive"))
      (node (ref "R3") (pin "2") (pintype "passive"))
    )
    (net (code "122") (name "VDD") (class "Default")
      (node (ref "C14") (pin "1") (pinfunction "1_1") (pintype "passive"))
      (node (ref "C15") (pin "1") (pinfunction "1_1") (pintype "passive"))
      (node (ref "C16") (pin "2") (pinfunction "2_2") (pintype "passive"))
      (node (ref "C19") (pin "1") (pinfunction "1_1") (pintype "passive"))
      (node (ref "C22") (pin "1") (pinfunction "1_1") (pintype "passive"))
      (node (ref "C23") (pin "1") (pinfunction "1_1") (pintype "passive"))
      (node (ref "C51") (pin "1") (pinfunction "1_1") (pintype "passive"))
      (node (ref "P5") (pin "1") (pinfunction "1_1") (pintype "passive"))
      (node (ref "P5") (pin "2") (pinfunction "2_2") (pintype "passive"))
      (node (ref "P5") (pin "3") (pinfunction "3_3") (pintype "passive"))
      (node (ref "P5") (pin "4") (pinfunction "4_4") (pintype "passive"))
      (node (ref "R11") (pin "1") (pintype "passive"))
      (node (ref "R12") (pin "1") (pintype "passive"))
      (node (ref "R8") (pin "1") (pinfunction "1_1") (pintype "passive"))
      (node (ref "R9") (pin "2") (pinfunction "2_2") (pintype "passive"))
      (node (ref "U3") (pin "16") (pinfunction "VDDA_16") (pintype "power_in"))
      (node (ref "U3") (pin "17") (pinfunction "VDD_17") (pintype "power_in"))
      (node (ref "U3") (pin "38") (pinfunction "VDD_38") (pintype "power_in"))
      (node (ref "U3") (pin "58") (pinfunction "VDD_58") (pintype "power_in"))
      (node (ref "U3") (pin "76") (pinfunction "VDD_76") (pintype "power_in"))
      (node (ref "U7") (pin "4") (pinfunction "VDD_4") (pintype "power_in"))
    )
    (net (code "123") (name "unconnected-(P2-D+-PadA6)") (class "Default")
      (node (ref "P2") (pin "A6") (pinfunction "D+_A6") (pintype "bidirectional+no_connect"))
    )
    (net (code "124") (name "unconnected-(P2-D+-PadB6)") (class "Default")
      (node (ref "P2") (pin "B6") (pinfunction "D+_B6") (pintype "bidirectional+no_connect"))
    )
    (net (code "125") (name "unconnected-(P2-D--PadA7)") (class "Default")
      (node (ref "P2") (pin "A7") (pinfunction "D-_A7") (pintype "bidirectional+no_connect"))
    )
    (net (code "126") (name "unconnected-(P2-D--PadB7)") (class "Default")
      (node (ref "P2") (pin "B7") (pinfunction "D-_B7") (pintype "bidirectional+no_connect"))
    )
    (net (code "127") (name "unconnected-(P2-RFU1-PadA8)") (class "Default")
      (node (ref "P2") (pin "A8") (pinfunction "RFU1_A8") (pintype "bidirectional+no_connect"))
    )
    (net (code "128") (name "unconnected-(P2-RFU1-PadB8)") (class "Default")
      (node (ref "P2") (pin "B8") (pinfunction "RFU1_B8") (pintype "bidirectional+no_connect"))
    )
    (net (code "129") (name "unconnected-(S1-NO-Pad3)") (class "Default")
      (node (ref "S1") (pin "3") (pinfunction "NO_3") (pintype "passive"))
    )
    (net (code "130") (name "unconnected-(U1-NC.-Pad2)") (class "Default")
      (node (ref "U1") (pin "2") (pinfunction "NC._2") (pintype "passive"))
    )
    (net (code "131") (name "unconnected-(U1-NC.-Pad3)") (class "Default")
      (node (ref "U1") (pin "3") (pinfunction "NC._3") (pintype "passive"))
    )
    (net (code "132") (name "unconnected-(U2-NC.-Pad1)") (class "Default")
      (node (ref "U2") (pin "1") (pinfunction "NC._1") (pintype "passive+no_connect"))
    )
  )
)
